# twip-mb1.net
KiCad netlist of a schematic drawn in EAGLE
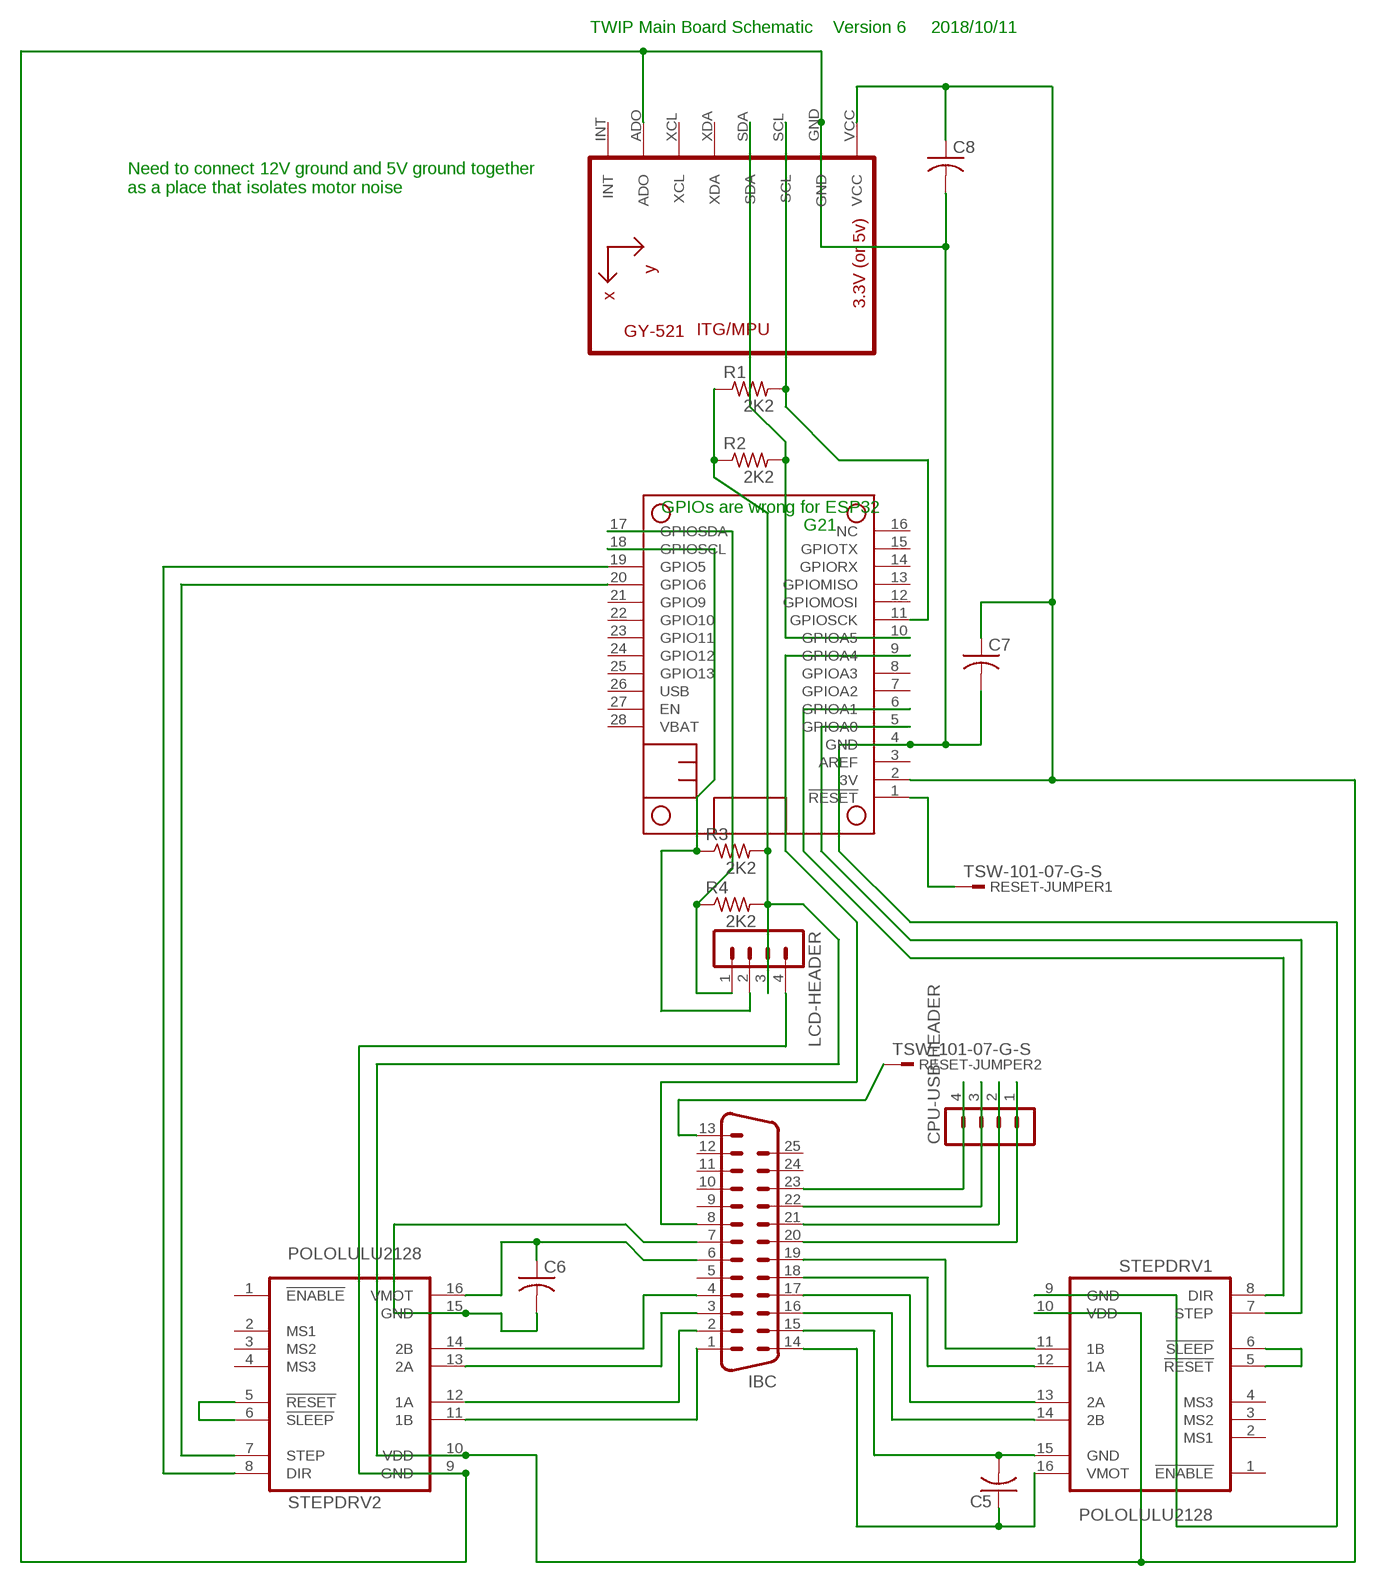
[diagram p0: schematic, sheet 1]

(export (version "E")
  (design (tool "Eeschema 10.0.6"))
  (components
    (comp (ref "C5")
      (value "C-US050-024X044")
      (footprint "eagle-import:C050-024X044")
      (libsource (lib "eagle-import") (part "C-US050-024X044"))
    )
    (comp (ref "C6")
      (value "C-US050-024X044")
      (footprint "eagle-import:C050-024X044")
      (libsource (lib "eagle-import") (part "C-US050-024X044"))
    )
    (comp (ref "C7")
      (value "C-US050-024X044")
      (footprint "eagle-import:C050-024X044")
      (libsource (lib "eagle-import") (part "C-US050-024X044"))
    )
    (comp (ref "C8")
      (value "C-US050-024X044")
      (footprint "eagle-import:C050-024X044")
      (libsource (lib "eagle-import") (part "C-US050-024X044"))
    )
    (comp (ref "CPU-USB-HEADER")
      (value "MA04-1")
      (footprint "eagle-import:MA04-1")
      (libsource (lib "eagle-import") (part "MA04-1"))
    )
    (comp (ref "IBC")
      (value "M25VP")
      (footprint "eagle-import:M25VP")
      (libsource (lib "eagle-import") (part "M25VP"))
    )
    (comp (ref "LCD-HEADER")
      (value "MA04-1")
      (footprint "eagle-import:MA04-1")
      (libsource (lib "eagle-import") (part "MA04-1"))
    )
    (comp (ref "MS2")
      (value "FEATHERWING_NOHOLES")
      (footprint "eagle-import:FEATHERWING_NOHOLES")
      (libsource (lib "eagle-import") (part "FEATHERWING_NOHOLES"))
    )
    (comp (ref "R1")
      (value "2K2")
      (footprint "eagle-import:0309_12")
      (libsource (lib "eagle-import") (part "R-US_0309/12"))
    )
    (comp (ref "R2")
      (value "2K2")
      (footprint "eagle-import:0309_12")
      (libsource (lib "eagle-import") (part "R-US_0309/12"))
    )
    (comp (ref "R3")
      (value "2K2")
      (footprint "eagle-import:0309_12")
      (libsource (lib "eagle-import") (part "R-US_0309/12"))
    )
    (comp (ref "R4")
      (value "2K2")
      (footprint "eagle-import:0309_12")
      (libsource (lib "eagle-import") (part "R-US_0309/12"))
    )
    (comp (ref "RESET-JUMPER1")
      (value "TSW-101-07-G-S")
      (footprint "eagle-import:TSW-101-XX-G-S")
      (fields (field (name "MF") "Samtec Inc."))
      (libsource (lib "eagle-import") (part "TSW-101--G-S07"))
    )
    (comp (ref "RESET-JUMPER2")
      (value "TSW-101-07-G-S")
      (footprint "eagle-import:TSW-101-XX-G-S")
      (fields (field (name "MF") "Samtec Inc."))
      (libsource (lib "eagle-import") (part "TSW-101--G-S07"))
    )
    (comp (ref "STEPDRV1")
      (value "POLOLULU2128")
      (footprint "eagle-import:POLOLULU2128")
      (libsource (lib "eagle-import") (part "POLOLULU2128"))
    )
    (comp (ref "STEPDRV2")
      (value "POLOLULU2128")
      (footprint "eagle-import:POLOLULU2128")
      (libsource (lib "eagle-import") (part "POLOLULU2128"))
    )
    (comp (ref "U1")
      (value "GY-521MPU6050")
      (footprint "eagle-import:GY-521")
      (libsource (lib "eagle-import") (part "GY-521MPU6050"))
    )
  )
  (nets
    (net (code "1") (name "/USB") (class "Default")
      (node (ref "MS2") (pin "26") (pinfunction "USB_26") (pintype "power_in"))
    )
    (net (code "2") (name "/VBAT") (class "Default")
      (node (ref "MS2") (pin "28") (pinfunction "VBAT_28") (pintype "power_in"))
    )
    (net (code "3") (name "Net-(C5-Pad2)") (class "Default")
      (node (ref "C5") (pin "2") (pinfunction "2_2") (pintype "passive"))
      (node (ref "IBC") (pin "15") (pinfunction "15_15") (pintype "passive"))
      (node (ref "STEPDRV1") (pin "15") (pinfunction "GND_15") (pintype "power_in"))
    )
    (net (code "4") (name "Net-(C6-Pad2)") (class "Default")
      (node (ref "C6") (pin "2") (pinfunction "2_2") (pintype "passive"))
      (node (ref "IBC") (pin "7") (pinfunction "7_7") (pintype "passive"))
      (node (ref "STEPDRV2") (pin "15") (pinfunction "GND_15") (pintype "power_in"))
    )
    (net (code "5") (name "Net-(CPU-USB-HEADER-Pad1)") (class "Default")
      (node (ref "CPU-USB-HEADER") (pin "1") (pinfunction "1_1") (pintype "passive"))
      (node (ref "IBC") (pin "20") (pinfunction "20_20") (pintype "passive"))
    )
    (net (code "6") (name "Net-(CPU-USB-HEADER-Pad2)") (class "Default")
      (node (ref "CPU-USB-HEADER") (pin "2") (pinfunction "2_2") (pintype "passive"))
      (node (ref "IBC") (pin "21") (pinfunction "21_21") (pintype "passive"))
    )
    (net (code "7") (name "Net-(CPU-USB-HEADER-Pad3)") (class "Default")
      (node (ref "CPU-USB-HEADER") (pin "3") (pinfunction "3_3") (pintype "passive"))
      (node (ref "IBC") (pin "22") (pinfunction "22_22") (pintype "passive"))
    )
    (net (code "8") (name "Net-(CPU-USB-HEADER-Pad4)") (class "Default")
      (node (ref "CPU-USB-HEADER") (pin "4") (pinfunction "4_4") (pintype "passive"))
      (node (ref "IBC") (pin "23") (pinfunction "23_23") (pintype "passive"))
    )
    (net (code "9") (name "Net-(IBC-Pad13)") (class "Default")
      (node (ref "IBC") (pin "13") (pinfunction "13_13") (pintype "passive"))
      (node (ref "RESET-JUMPER2") (pin "1") (pinfunction "1_1") (pintype "passive"))
    )
    (net (code "10") (name "Net-(MS2-3V)") (class "Default")
      (node (ref "C7") (pin "1") (pinfunction "1_1") (pintype "passive"))
      (node (ref "C8") (pin "1") (pinfunction "1_1") (pintype "passive"))
      (node (ref "LCD-HEADER") (pin "3") (pinfunction "3_3") (pintype "passive"))
      (node (ref "MS2") (pin "2") (pinfunction "3V_2") (pintype "power_in"))
      (node (ref "R1") (pin "1") (pinfunction "1_1") (pintype "passive"))
      (node (ref "R2") (pin "1") (pinfunction "1_1") (pintype "passive"))
      (node (ref "R3") (pin "2") (pinfunction "2_2") (pintype "passive"))
      (node (ref "R4") (pin "2") (pinfunction "2_2") (pintype "passive"))
      (node (ref "STEPDRV1") (pin "10") (pinfunction "VDD_10") (pintype "power_in"))
      (node (ref "STEPDRV2") (pin "10") (pinfunction "VDD_10") (pintype "power_in"))
      (node (ref "U1") (pin "VCC") (pinfunction "VCC_VCC") (pintype "bidirectional"))
    )
    (net (code "11") (name "Net-(MS2-GND)") (class "Default")
      (node (ref "C7") (pin "2") (pinfunction "2_2") (pintype "passive"))
      (node (ref "C8") (pin "2") (pinfunction "2_2") (pintype "passive"))
      (node (ref "LCD-HEADER") (pin "4") (pinfunction "4_4") (pintype "passive"))
      (node (ref "MS2") (pin "4") (pinfunction "GND_4") (pintype "power_in"))
      (node (ref "STEPDRV1") (pin "9") (pinfunction "GND_9") (pintype "power_in"))
      (node (ref "STEPDRV2") (pin "9") (pinfunction "GND_9") (pintype "power_in"))
      (node (ref "U1") (pin "ADO") (pinfunction "ADO_ADO") (pintype "bidirectional"))
      (node (ref "U1") (pin "GND") (pinfunction "GND_GND") (pintype "bidirectional"))
    )
    (net (code "12") (name "Net-(MS2-GPIO5)") (class "Default")
      (node (ref "MS2") (pin "19") (pinfunction "GPIO5_19") (pintype "bidirectional"))
      (node (ref "STEPDRV2") (pin "8") (pinfunction "DIR_8") (pintype "input"))
    )
    (net (code "13") (name "Net-(MS2-GPIO6)") (class "Default")
      (node (ref "MS2") (pin "20") (pinfunction "GPIO6_20") (pintype "bidirectional"))
      (node (ref "STEPDRV2") (pin "7") (pinfunction "STEP_7") (pintype "input"))
    )
    (net (code "14") (name "Net-(MS2-GPIOA0)") (class "Default")
      (node (ref "MS2") (pin "5") (pinfunction "GPIOA0_5") (pintype "bidirectional"))
      (node (ref "STEPDRV1") (pin "7") (pinfunction "STEP_7") (pintype "input"))
    )
    (net (code "15") (name "Net-(MS2-GPIOA1)") (class "Default")
      (node (ref "MS2") (pin "6") (pinfunction "GPIOA1_6") (pintype "bidirectional"))
      (node (ref "STEPDRV1") (pin "8") (pinfunction "DIR_8") (pintype "input"))
    )
    (net (code "16") (name "Net-(MS2-GPIOA4)") (class "Default")
      (node (ref "IBC") (pin "8") (pinfunction "8_8") (pintype "passive"))
      (node (ref "MS2") (pin "9") (pinfunction "GPIOA4_9") (pintype "bidirectional"))
    )
    (net (code "17") (name "Net-(MS2-GPIOA5)") (class "Default")
      (node (ref "MS2") (pin "10") (pinfunction "GPIOA5_10") (pintype "bidirectional"))
      (node (ref "R2") (pin "2") (pinfunction "2_2") (pintype "passive"))
      (node (ref "U1") (pin "SDA") (pinfunction "SDA_SDA") (pintype "bidirectional"))
    )
    (net (code "18") (name "Net-(MS2-GPIOSCK)") (class "Default")
      (node (ref "MS2") (pin "11") (pinfunction "GPIOSCK_11") (pintype "bidirectional"))
      (node (ref "R1") (pin "2") (pinfunction "2_2") (pintype "passive"))
      (node (ref "U1") (pin "SCL") (pinfunction "SCL_SCL") (pintype "bidirectional"))
    )
    (net (code "19") (name "Net-(MS2-GPIOSCL)") (class "Default")
      (node (ref "LCD-HEADER") (pin "2") (pinfunction "2_2") (pintype "passive"))
      (node (ref "MS2") (pin "18") (pinfunction "GPIOSCL_18") (pintype "bidirectional"))
      (node (ref "R3") (pin "1") (pinfunction "1_1") (pintype "passive"))
    )
    (net (code "20") (name "Net-(MS2-GPIOSDA)") (class "Default")
      (node (ref "LCD-HEADER") (pin "1") (pinfunction "1_1") (pintype "passive"))
      (node (ref "MS2") (pin "17") (pinfunction "GPIOSDA_17") (pintype "bidirectional"))
      (node (ref "R4") (pin "1") (pinfunction "1_1") (pintype "passive"))
    )
    (net (code "21") (name "Net-(MS2-~{RESET})") (class "Default")
      (node (ref "MS2") (pin "1") (pinfunction "~{RESET}_1") (pintype "input"))
      (node (ref "RESET-JUMPER1") (pin "1") (pinfunction "1_1") (pintype "passive"))
    )
    (net (code "22") (name "Net-(STEPDRV1-1A)") (class "Default")
      (node (ref "IBC") (pin "18") (pinfunction "18_18") (pintype "passive"))
      (node (ref "STEPDRV1") (pin "12") (pinfunction "1A_12") (pintype "output"))
    )
    (net (code "23") (name "Net-(STEPDRV1-1B)") (class "Default")
      (node (ref "IBC") (pin "19") (pinfunction "19_19") (pintype "passive"))
      (node (ref "STEPDRV1") (pin "11") (pinfunction "1B_11") (pintype "output"))
    )
    (net (code "24") (name "Net-(STEPDRV1-2A)") (class "Default")
      (node (ref "IBC") (pin "17") (pinfunction "17_17") (pintype "passive"))
      (node (ref "STEPDRV1") (pin "13") (pinfunction "2A_13") (pintype "output"))
    )
    (net (code "25") (name "Net-(STEPDRV1-2B)") (class "Default")
      (node (ref "IBC") (pin "16") (pinfunction "16_16") (pintype "passive"))
      (node (ref "STEPDRV1") (pin "14") (pinfunction "2B_14") (pintype "output"))
    )
    (net (code "26") (name "Net-(STEPDRV1-VMOT)") (class "Default")
      (node (ref "C5") (pin "1") (pinfunction "1_1") (pintype "passive"))
      (node (ref "IBC") (pin "14") (pinfunction "14_14") (pintype "passive"))
      (node (ref "STEPDRV1") (pin "16") (pinfunction "VMOT_16") (pintype "power_in"))
    )
    (net (code "27") (name "Net-(STEPDRV1-~{RESET})") (class "Default")
      (node (ref "STEPDRV1") (pin "5") (pinfunction "~{RESET}_5") (pintype "input"))
      (node (ref "STEPDRV1") (pin "6") (pinfunction "~{SLEEP}_6") (pintype "input"))
    )
    (net (code "28") (name "Net-(STEPDRV2-1A)") (class "Default")
      (node (ref "IBC") (pin "2") (pinfunction "2_2") (pintype "passive"))
      (node (ref "STEPDRV2") (pin "12") (pinfunction "1A_12") (pintype "output"))
    )
    (net (code "29") (name "Net-(STEPDRV2-1B)") (class "Default")
      (node (ref "IBC") (pin "1") (pinfunction "1_1") (pintype "passive"))
      (node (ref "STEPDRV2") (pin "11") (pinfunction "1B_11") (pintype "output"))
    )
    (net (code "30") (name "Net-(STEPDRV2-2A)") (class "Default")
      (node (ref "IBC") (pin "3") (pinfunction "3_3") (pintype "passive"))
      (node (ref "STEPDRV2") (pin "13") (pinfunction "2A_13") (pintype "output"))
    )
    (net (code "31") (name "Net-(STEPDRV2-2B)") (class "Default")
      (node (ref "IBC") (pin "4") (pinfunction "4_4") (pintype "passive"))
      (node (ref "STEPDRV2") (pin "14") (pinfunction "2B_14") (pintype "output"))
    )
    (net (code "32") (name "Net-(STEPDRV2-VMOT)") (class "Default")
      (node (ref "C6") (pin "1") (pinfunction "1_1") (pintype "passive"))
      (node (ref "IBC") (pin "6") (pinfunction "6_6") (pintype "passive"))
      (node (ref "STEPDRV2") (pin "16") (pinfunction "VMOT_16") (pintype "power_in"))
    )
    (net (code "33") (name "Net-(STEPDRV2-~{RESET})") (class "Default")
      (node (ref "STEPDRV2") (pin "5") (pinfunction "~{RESET}_5") (pintype "input"))
      (node (ref "STEPDRV2") (pin "6") (pinfunction "~{SLEEP}_6") (pintype "input"))
    )
    (net (code "34") (name "unconnected-(IBC-Pad5)") (class "Default")
      (node (ref "IBC") (pin "5") (pinfunction "5_5") (pintype "passive"))
    )
    (net (code "35") (name "unconnected-(IBC-Pad9)") (class "Default")
      (node (ref "IBC") (pin "9") (pinfunction "9_9") (pintype "passive"))
    )
    (net (code "36") (name "unconnected-(IBC-Pad10)") (class "Default")
      (node (ref "IBC") (pin "10") (pinfunction "10_10") (pintype "passive"))
    )
    (net (code "37") (name "unconnected-(IBC-Pad11)") (class "Default")
      (node (ref "IBC") (pin "11") (pinfunction "11_11") (pintype "passive"))
    )
    (net (code "38") (name "unconnected-(IBC-Pad12)") (class "Default")
      (node (ref "IBC") (pin "12") (pinfunction "12_12") (pintype "passive"))
    )
    (net (code "39") (name "unconnected-(IBC-Pad24)") (class "Default")
      (node (ref "IBC") (pin "24") (pinfunction "24_24") (pintype "passive"))
    )
    (net (code "40") (name "unconnected-(IBC-Pad25)") (class "Default")
      (node (ref "IBC") (pin "25") (pinfunction "25_25") (pintype "passive"))
    )
    (net (code "41") (name "unconnected-(MS2-AREF-Pad3)") (class "Default")
      (node (ref "MS2") (pin "3") (pinfunction "AREF_3") (pintype "passive"))
    )
    (net (code "42") (name "unconnected-(MS2-EN-Pad27)") (class "Default")
      (node (ref "MS2") (pin "27") (pinfunction "EN_27") (pintype "passive"))
    )
    (net (code "43") (name "unconnected-(MS2-GPIO9-Pad21)") (class "Default")
      (node (ref "MS2") (pin "21") (pinfunction "GPIO9_21") (pintype "bidirectional"))
    )
    (net (code "44") (name "unconnected-(MS2-GPIO10-Pad22)") (class "Default")
      (node (ref "MS2") (pin "22") (pinfunction "GPIO10_22") (pintype "bidirectional"))
    )
    (net (code "45") (name "unconnected-(MS2-GPIO11-Pad23)") (class "Default")
      (node (ref "MS2") (pin "23") (pinfunction "GPIO11_23") (pintype "bidirectional"))
    )
    (net (code "46") (name "unconnected-(MS2-GPIO12-Pad24)") (class "Default")
      (node (ref "MS2") (pin "24") (pinfunction "GPIO12_24") (pintype "bidirectional"))
    )
    (net (code "47") (name "unconnected-(MS2-GPIO13-Pad25)") (class "Default")
      (node (ref "MS2") (pin "25") (pinfunction "GPIO13_25") (pintype "bidirectional"))
    )
    (net (code "48") (name "unconnected-(MS2-GPIOA2-Pad7)") (class "Default")
      (node (ref "MS2") (pin "7") (pinfunction "GPIOA2_7") (pintype "bidirectional"))
    )
    (net (code "49") (name "unconnected-(MS2-GPIOA3-Pad8)") (class "Default")
      (node (ref "MS2") (pin "8") (pinfunction "GPIOA3_8") (pintype "bidirectional"))
    )
    (net (code "50") (name "unconnected-(MS2-GPIOMISO-Pad13)") (class "Default")
      (node (ref "MS2") (pin "13") (pinfunction "GPIOMISO_13") (pintype "bidirectional"))
    )
    (net (code "51") (name "unconnected-(MS2-GPIOMOSI-Pad12)") (class "Default")
      (node (ref "MS2") (pin "12") (pinfunction "GPIOMOSI_12") (pintype "bidirectional"))
    )
    (net (code "52") (name "unconnected-(MS2-GPIORX-Pad14)") (class "Default")
      (node (ref "MS2") (pin "14") (pinfunction "GPIORX_14") (pintype "bidirectional"))
    )
    (net (code "53") (name "unconnected-(MS2-GPIOTX-Pad15)") (class "Default")
      (node (ref "MS2") (pin "15") (pinfunction "GPIOTX_15") (pintype "bidirectional"))
    )
    (net (code "54") (name "unconnected-(MS2-NC-Pad16)") (class "Default")
      (node (ref "MS2") (pin "16") (pinfunction "NC_16") (pintype "passive"))
    )
    (net (code "55") (name "unconnected-(STEPDRV1-MS1-Pad2)") (class "Default")
      (node (ref "STEPDRV1") (pin "2") (pinfunction "MS1_2") (pintype "input"))
    )
    (net (code "56") (name "unconnected-(STEPDRV1-MS2-Pad3)") (class "Default")
      (node (ref "STEPDRV1") (pin "3") (pinfunction "MS2_3") (pintype "input"))
    )
    (net (code "57") (name "unconnected-(STEPDRV1-MS3-Pad4)") (class "Default")
      (node (ref "STEPDRV1") (pin "4") (pinfunction "MS3_4") (pintype "input"))
    )
    (net (code "58") (name "unconnected-(STEPDRV1-~{ENABLE}-Pad1)") (class "Default")
      (node (ref "STEPDRV1") (pin "1") (pinfunction "~{ENABLE}_1") (pintype "input"))
    )
    (net (code "59") (name "unconnected-(STEPDRV2-MS1-Pad2)") (class "Default")
      (node (ref "STEPDRV2") (pin "2") (pinfunction "MS1_2") (pintype "input"))
    )
    (net (code "60") (name "unconnected-(STEPDRV2-MS2-Pad3)") (class "Default")
      (node (ref "STEPDRV2") (pin "3") (pinfunction "MS2_3") (pintype "input"))
    )
    (net (code "61") (name "unconnected-(STEPDRV2-MS3-Pad4)") (class "Default")
      (node (ref "STEPDRV2") (pin "4") (pinfunction "MS3_4") (pintype "input"))
    )
    (net (code "62") (name "unconnected-(STEPDRV2-~{ENABLE}-Pad1)") (class "Default")
      (node (ref "STEPDRV2") (pin "1") (pinfunction "~{ENABLE}_1") (pintype "input"))
    )
    (net (code "63") (name "unconnected-(U1-PadINT)") (class "Default")
      (node (ref "U1") (pin "INT") (pinfunction "INT_INT") (pintype "bidirectional"))
    )
    (net (code "64") (name "unconnected-(U1-PadXCL)") (class "Default")
      (node (ref "U1") (pin "XCL") (pinfunction "XCL_XCL") (pintype "bidirectional"))
    )
    (net (code "65") (name "unconnected-(U1-PadXDA)") (class "Default")
      (node (ref "U1") (pin "XDA") (pinfunction "XDA_XDA") (pintype "bidirectional"))
    )
  )
)
